# slave-board.net
KiCad netlist of a schematic drawn in EAGLE
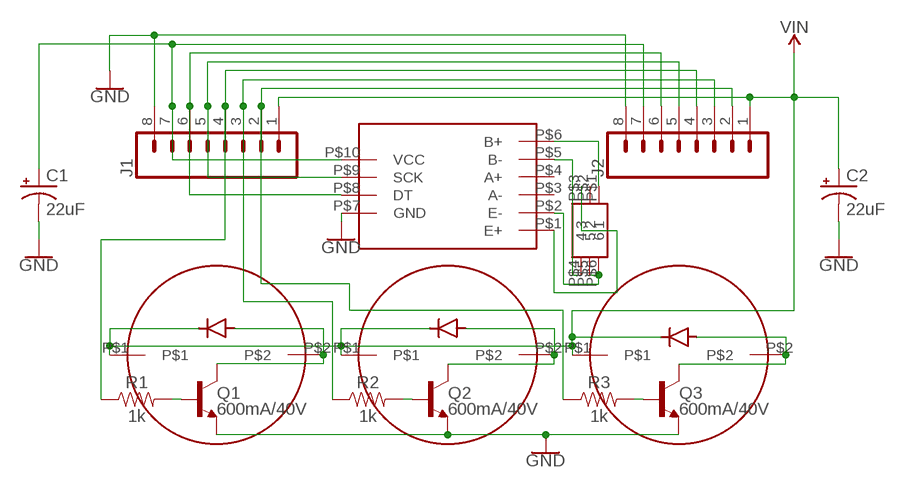
[diagram p0: schematic, sheet 1]

(export (version "E")
  (design (tool "Eeschema 10.0.6"))
  (components
    (comp (ref "C1")
      (value "22uF")
      (footprint "eagle-import:PANASONIC_C")
      (libsource (lib "eagle-import") (part "22UF-POLAR-PANASONIC_C-35V-20%"))
    )
    (comp (ref "C2")
      (value "22uF")
      (footprint "eagle-import:PANASONIC_C")
      (libsource (lib "eagle-import") (part "22UF-POLAR-PANASONIC_C-35V-20%"))
    )
    (comp (ref "J1")
      (value "CONN_08\"")
      (footprint "eagle-import:1X08")
      (libsource (lib "eagle-import") (part "CONN_08{dblquote}"))
    )
    (comp (ref "J2")
      (value "CONN_08\"")
      (footprint "eagle-import:1X08")
      (libsource (lib "eagle-import") (part "CONN_08{dblquote}"))
    )
    (comp (ref "Q1")
      (value "600mA/40V")
      (footprint "eagle-import:SOT23-3")
      (libsource (lib "eagle-import") (part "TRANS_NPN-MMBT2222AL"))
    )
    (comp (ref "Q2")
      (value "600mA/40V")
      (footprint "eagle-import:SOT23-3")
      (libsource (lib "eagle-import") (part "TRANS_NPN-MMBT2222AL"))
    )
    (comp (ref "Q3")
      (value "600mA/40V")
      (footprint "eagle-import:SOT23-3")
      (libsource (lib "eagle-import") (part "TRANS_NPN-MMBT2222AL"))
    )
    (comp (ref "R1")
      (value "1k")
      (footprint "eagle-import:0603")
      (libsource (lib "eagle-import") (part "1KOHM-0603-1/10W-1%"))
    )
    (comp (ref "R2")
      (value "1k")
      (footprint "eagle-import:0603")
      (libsource (lib "eagle-import") (part "1KOHM-0603-1/10W-1%"))
    )
    (comp (ref "R3")
      (value "1k")
      (footprint "eagle-import:0603")
      (libsource (lib "eagle-import") (part "1KOHM-0603-1/10W-1%"))
    )
    (comp (ref "U$1")
      (value "HX711")
      (footprint "eagle-import:HX711")
      (libsource (lib "eagle-import") (part "HX711"))
    )
    (comp (ref "U$2")
      (value "CJV23-SOLENOID-VALVE")
      (footprint "eagle-import:CJV23")
      (libsource (lib "eagle-import") (part "CJV23-SOLENOID-VALVE"))
    )
    (comp (ref "U$3")
      (value "CJV23-SOLENOID-VALVE")
      (footprint "eagle-import:CJV23")
      (libsource (lib "eagle-import") (part "CJV23-SOLENOID-VALVE"))
    )
    (comp (ref "U$4")
      (value "CJV23-SOLENOID-VALVE")
      (footprint "eagle-import:CJV23")
      (libsource (lib "eagle-import") (part "CJV23-SOLENOID-VALVE"))
    )
    (comp (ref "U$5")
      (value "IN4148")
      (footprint "eagle-import:IN4148")
      (libsource (lib "eagle-import") (part "IN4148"))
    )
    (comp (ref "U$6")
      (value "IN4148")
      (footprint "eagle-import:IN4148")
      (libsource (lib "eagle-import") (part "IN4148"))
    )
    (comp (ref "U$7")
      (value "IN4148")
      (footprint "eagle-import:IN4148")
      (libsource (lib "eagle-import") (part "IN4148"))
    )
    (comp (ref "U$8")
      (value "2SMPP-03")
      (footprint "eagle-import:2SMPP-03")
      (libsource (lib "eagle-import") (part "2SMPP-03"))
    )
  )
  (nets
    (net (code "1") (name "GND") (class "Default")
      (node (ref "C1") (pin "-") (pinfunction "-_-") (pintype "passive"))
      (node (ref "C2") (pin "-") (pinfunction "-_-") (pintype "passive"))
      (node (ref "J1") (pin "8") (pinfunction "8_8") (pintype "passive"))
      (node (ref "J2") (pin "8") (pinfunction "8_8") (pintype "passive"))
      (node (ref "Q1") (pin "2") (pinfunction "E_2") (pintype "passive"))
      (node (ref "Q2") (pin "2") (pinfunction "E_2") (pintype "passive"))
      (node (ref "Q3") (pin "2") (pinfunction "E_2") (pintype "passive"))
      (node (ref "U$1") (pin "P$7") (pinfunction "GND_P$7") (pintype "bidirectional"))
    )
    (net (code "2") (name "Net-(J1-Pad2)") (class "Default")
      (node (ref "J1") (pin "2") (pinfunction "2_2") (pintype "passive"))
      (node (ref "J2") (pin "2") (pinfunction "2_2") (pintype "passive"))
      (node (ref "R3") (pin "1") (pinfunction "1_1") (pintype "passive"))
    )
    (net (code "3") (name "Net-(J1-Pad3)") (class "Default")
      (node (ref "J1") (pin "3") (pinfunction "3_3") (pintype "passive"))
      (node (ref "J2") (pin "3") (pinfunction "3_3") (pintype "passive"))
      (node (ref "R2") (pin "1") (pinfunction "1_1") (pintype "passive"))
    )
    (net (code "4") (name "Net-(J1-Pad4)") (class "Default")
      (node (ref "J1") (pin "4") (pinfunction "4_4") (pintype "passive"))
      (node (ref "J2") (pin "4") (pinfunction "4_4") (pintype "passive"))
      (node (ref "R1") (pin "1") (pinfunction "1_1") (pintype "passive"))
    )
    (net (code "5") (name "Net-(Q1-B)") (class "Default")
      (node (ref "Q1") (pin "1") (pinfunction "B_1") (pintype "passive"))
      (node (ref "R1") (pin "2") (pinfunction "2_2") (pintype "passive"))
    )
    (net (code "6") (name "Net-(Q1-C)") (class "Default")
      (node (ref "Q1") (pin "3") (pinfunction "C_3") (pintype "passive"))
      (node (ref "U$2") (pin "P$2") (pinfunction "P$2_P$2") (pintype "bidirectional"))
      (node (ref "U$5") (pin "P$2") (pinfunction "P$2_P$2") (pintype "bidirectional"))
    )
    (net (code "7") (name "Net-(Q2-B)") (class "Default")
      (node (ref "Q2") (pin "1") (pinfunction "B_1") (pintype "passive"))
      (node (ref "R2") (pin "2") (pinfunction "2_2") (pintype "passive"))
    )
    (net (code "8") (name "Net-(Q2-C)") (class "Default")
      (node (ref "Q2") (pin "3") (pinfunction "C_3") (pintype "passive"))
      (node (ref "U$3") (pin "P$2") (pinfunction "P$2_P$2") (pintype "bidirectional"))
      (node (ref "U$6") (pin "P$2") (pinfunction "P$2_P$2") (pintype "bidirectional"))
    )
    (net (code "9") (name "Net-(Q3-B)") (class "Default")
      (node (ref "Q3") (pin "1") (pinfunction "B_1") (pintype "passive"))
      (node (ref "R3") (pin "2") (pinfunction "2_2") (pintype "passive"))
    )
    (net (code "10") (name "Net-(Q3-C)") (class "Default")
      (node (ref "Q3") (pin "3") (pinfunction "C_3") (pintype "passive"))
      (node (ref "U$4") (pin "P$2") (pinfunction "P$2_P$2") (pintype "bidirectional"))
      (node (ref "U$7") (pin "P$2") (pinfunction "P$2_P$2") (pintype "bidirectional"))
    )
    (net (code "11") (name "Net-(U$1-B+)") (class "Default")
      (node (ref "U$1") (pin "P$6") (pinfunction "B+_P$6") (pintype "bidirectional"))
      (node (ref "U$8") (pin "P$1") (pinfunction "1_P$1") (pintype "bidirectional"))
    )
    (net (code "12") (name "Net-(U$1-B-)") (class "Default")
      (node (ref "U$1") (pin "P$5") (pinfunction "B-_P$5") (pintype "bidirectional"))
      (node (ref "U$8") (pin "P$4") (pinfunction "4_P$4") (pintype "bidirectional"))
    )
    (net (code "13") (name "Net-(U$1-DT)") (class "Default")
      (node (ref "J1") (pin "6") (pinfunction "6_6") (pintype "passive"))
      (node (ref "J2") (pin "6") (pinfunction "6_6") (pintype "passive"))
      (node (ref "U$1") (pin "P$8") (pinfunction "DT_P$8") (pintype "bidirectional"))
    )
    (net (code "14") (name "Net-(U$1-E+)") (class "Default")
      (node (ref "U$1") (pin "P$1") (pinfunction "E+_P$1") (pintype "bidirectional"))
      (node (ref "U$8") (pin "P$3") (pinfunction "3_P$3") (pintype "bidirectional"))
    )
    (net (code "15") (name "Net-(U$1-E-)") (class "Default")
      (node (ref "U$1") (pin "P$2") (pinfunction "E-_P$2") (pintype "bidirectional"))
      (node (ref "U$8") (pin "P$5") (pinfunction "5_P$5") (pintype "bidirectional"))
      (node (ref "U$8") (pin "P$6") (pinfunction "6_P$6") (pintype "bidirectional"))
    )
    (net (code "16") (name "Net-(U$1-SCK)") (class "Default")
      (node (ref "J1") (pin "5") (pinfunction "5_5") (pintype "passive"))
      (node (ref "J2") (pin "5") (pinfunction "5_5") (pintype "passive"))
      (node (ref "U$1") (pin "P$9") (pinfunction "SCK_P$9") (pintype "bidirectional"))
    )
    (net (code "17") (name "Net-(U$1-VCC)") (class "Default")
      (node (ref "C1") (pin "+") (pinfunction "+_+") (pintype "passive"))
      (node (ref "J1") (pin "7") (pinfunction "7_7") (pintype "passive"))
      (node (ref "J2") (pin "7") (pinfunction "7_7") (pintype "passive"))
      (node (ref "U$1") (pin "P$10") (pinfunction "VCC_P$10") (pintype "bidirectional"))
    )
    (net (code "18") (name "VIN") (class "Default")
      (node (ref "C2") (pin "+") (pinfunction "+_+") (pintype "passive"))
      (node (ref "J1") (pin "1") (pinfunction "1_1") (pintype "passive"))
      (node (ref "J2") (pin "1") (pinfunction "1_1") (pintype "passive"))
      (node (ref "U$2") (pin "P$1") (pinfunction "P$1_P$1") (pintype "bidirectional"))
      (node (ref "U$3") (pin "P$1") (pinfunction "P$1_P$1") (pintype "bidirectional"))
      (node (ref "U$4") (pin "P$1") (pinfunction "P$1_P$1") (pintype "bidirectional"))
      (node (ref "U$5") (pin "P$1") (pinfunction "P$1_P$1") (pintype "bidirectional"))
      (node (ref "U$6") (pin "P$1") (pinfunction "P$1_P$1") (pintype "bidirectional"))
      (node (ref "U$7") (pin "P$1") (pinfunction "P$1_P$1") (pintype "bidirectional"))
    )
    (net (code "19") (name "unconnected-(U$1-A+-PadP$4)") (class "Default")
      (node (ref "U$1") (pin "P$4") (pinfunction "A+_P$4") (pintype "bidirectional"))
    )
    (net (code "20") (name "unconnected-(U$1-A--PadP$3)") (class "Default")
      (node (ref "U$1") (pin "P$3") (pinfunction "A-_P$3") (pintype "bidirectional"))
    )
    (net (code "21") (name "unconnected-(U$8-2-PadP$2)") (class "Default")
      (node (ref "U$8") (pin "P$2") (pinfunction "2_P$2") (pintype "bidirectional"))
    )
  )
)
